# 8x8v2.net
KiCad netlist of a schematic drawn in EAGLE
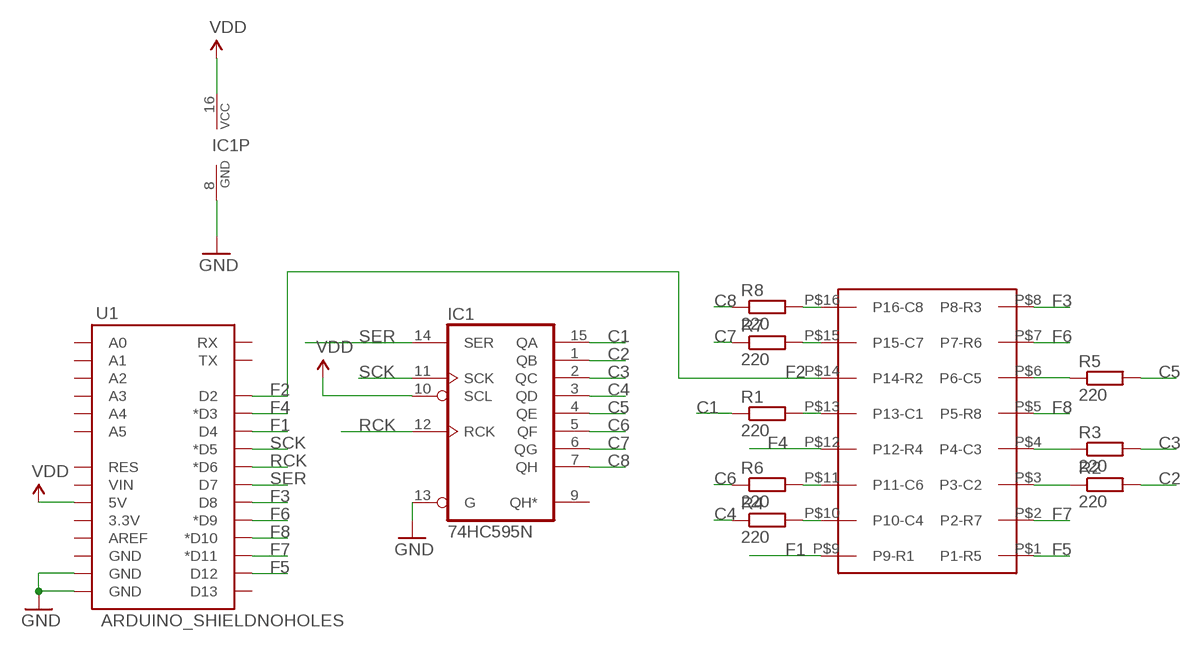
[diagram p0: schematic, sheet 1]

(export (version "E")
  (design (tool "Eeschema 10.0.6"))
  (components
    (comp (ref "IC1")
      (value "74HC595N")
      (footprint "eagle-import:DIL16")
      (libsource (lib "eagle-import") (part "74595NHC"))
    )
    (comp (ref "R1")
      (value "220")
      (footprint "eagle-import:0207_10")
      (libsource (lib "eagle-import") (part "R-EU_0207/10"))
    )
    (comp (ref "R2")
      (value "220")
      (footprint "eagle-import:0207_10")
      (libsource (lib "eagle-import") (part "R-EU_0207/10"))
    )
    (comp (ref "R3")
      (value "220")
      (footprint "eagle-import:0207_10")
      (libsource (lib "eagle-import") (part "R-EU_0207/10"))
    )
    (comp (ref "R4")
      (value "220")
      (footprint "eagle-import:0207_10")
      (libsource (lib "eagle-import") (part "R-EU_0207/10"))
    )
    (comp (ref "R5")
      (value "220")
      (footprint "eagle-import:0207_10")
      (libsource (lib "eagle-import") (part "R-EU_0207/10"))
    )
    (comp (ref "R6")
      (value "220")
      (footprint "eagle-import:0207_10")
      (libsource (lib "eagle-import") (part "R-EU_0207/10"))
    )
    (comp (ref "R7")
      (value "220")
      (footprint "eagle-import:0207_10")
      (libsource (lib "eagle-import") (part "R-EU_0207/10"))
    )
    (comp (ref "R8")
      (value "220")
      (footprint "eagle-import:0207_10")
      (libsource (lib "eagle-import") (part "R-EU_0207/10"))
    )
    (comp (ref "U$1")
      (value "MATRIX8X8")
      (footprint "eagle-import:MATRIX")
      (libsource (lib "eagle-import") (part "MATRIX8X8"))
    )
    (comp (ref "U1")
      (value "ARDUINO_SHIELDNOHOLES")
      (footprint "eagle-import:DUEMILANOVE_SHIELD_NOHOLES")
      (libsource (lib "eagle-import") (part "ARDUINO_SHIELDNOHOLES"))
    )
  )
  (nets
    (net (code "1") (name "/C1") (class "Default")
      (node (ref "IC1") (pin "15") (pinfunction "QA_15") (pintype "tri_state"))
      (node (ref "R1") (pin "1") (pinfunction "1_1") (pintype "passive"))
    )
    (net (code "2") (name "/C2") (class "Default")
      (node (ref "IC1") (pin "1") (pinfunction "QB_1") (pintype "tri_state"))
      (node (ref "R2") (pin "2") (pinfunction "2_2") (pintype "passive"))
    )
    (net (code "3") (name "/C3") (class "Default")
      (node (ref "IC1") (pin "2") (pinfunction "QC_2") (pintype "tri_state"))
      (node (ref "R3") (pin "2") (pinfunction "2_2") (pintype "passive"))
    )
    (net (code "4") (name "/C4") (class "Default")
      (node (ref "IC1") (pin "3") (pinfunction "QD_3") (pintype "tri_state"))
      (node (ref "R4") (pin "1") (pinfunction "1_1") (pintype "passive"))
    )
    (net (code "5") (name "/C5") (class "Default")
      (node (ref "IC1") (pin "4") (pinfunction "QE_4") (pintype "tri_state"))
      (node (ref "R5") (pin "2") (pinfunction "2_2") (pintype "passive"))
    )
    (net (code "6") (name "/C6") (class "Default")
      (node (ref "IC1") (pin "5") (pinfunction "QF_5") (pintype "tri_state"))
      (node (ref "R6") (pin "1") (pinfunction "1_1") (pintype "passive"))
    )
    (net (code "7") (name "/C7") (class "Default")
      (node (ref "IC1") (pin "6") (pinfunction "QG_6") (pintype "tri_state"))
      (node (ref "R7") (pin "1") (pinfunction "1_1") (pintype "passive"))
    )
    (net (code "8") (name "/C8") (class "Default")
      (node (ref "IC1") (pin "7") (pinfunction "QH_7") (pintype "tri_state"))
      (node (ref "R8") (pin "1") (pinfunction "1_1") (pintype "passive"))
    )
    (net (code "9") (name "/F1") (class "Default")
      (node (ref "U$1") (pin "P$9") (pinfunction "P9-R1_P$9") (pintype "bidirectional"))
      (node (ref "U1") (pin "D4") (pinfunction "D4_D4") (pintype "bidirectional"))
    )
    (net (code "10") (name "/F2") (class "Default")
      (node (ref "U$1") (pin "P$14") (pinfunction "P14-R2_P$14") (pintype "bidirectional"))
      (node (ref "U1") (pin "D2") (pinfunction "D2_D2") (pintype "bidirectional"))
    )
    (net (code "11") (name "/F3") (class "Default")
      (node (ref "U$1") (pin "P$8") (pinfunction "P8-R3_P$8") (pintype "bidirectional"))
      (node (ref "U1") (pin "D8") (pinfunction "D8_D8") (pintype "bidirectional"))
    )
    (net (code "12") (name "/F4") (class "Default")
      (node (ref "U$1") (pin "P$12") (pinfunction "P12-R4_P$12") (pintype "bidirectional"))
      (node (ref "U1") (pin "D3") (pinfunction "*D3_D3") (pintype "bidirectional"))
    )
    (net (code "13") (name "/F5") (class "Default")
      (node (ref "U$1") (pin "P$1") (pinfunction "P1-R5_P$1") (pintype "bidirectional"))
      (node (ref "U1") (pin "D12") (pinfunction "D12_D12") (pintype "bidirectional"))
    )
    (net (code "14") (name "/F6") (class "Default")
      (node (ref "U$1") (pin "P$7") (pinfunction "P7-R6_P$7") (pintype "bidirectional"))
      (node (ref "U1") (pin "D9") (pinfunction "*D9_D9") (pintype "bidirectional"))
    )
    (net (code "15") (name "/F7") (class "Default")
      (node (ref "U$1") (pin "P$2") (pinfunction "P2-R7_P$2") (pintype "bidirectional"))
      (node (ref "U1") (pin "D11") (pinfunction "*D11_D11") (pintype "bidirectional"))
    )
    (net (code "16") (name "/F8") (class "Default")
      (node (ref "U$1") (pin "P$5") (pinfunction "P5-R8_P$5") (pintype "bidirectional"))
      (node (ref "U1") (pin "D10") (pinfunction "*D10_D10") (pintype "bidirectional"))
    )
    (net (code "17") (name "/RCK") (class "Default")
      (node (ref "IC1") (pin "12") (pinfunction "RCK_12") (pintype "input"))
      (node (ref "U1") (pin "D6") (pinfunction "*D6_D6") (pintype "bidirectional"))
    )
    (net (code "18") (name "/SCK") (class "Default")
      (node (ref "IC1") (pin "11") (pinfunction "SCK_11") (pintype "input"))
      (node (ref "U1") (pin "D5") (pinfunction "*D5_D5") (pintype "bidirectional"))
    )
    (net (code "19") (name "/SER") (class "Default")
      (node (ref "IC1") (pin "14") (pinfunction "SER_14") (pintype "input"))
      (node (ref "U1") (pin "D7") (pinfunction "D7_D7") (pintype "bidirectional"))
    )
    (net (code "20") (name "GND") (class "Default")
      (node (ref "IC1") (pin "13") (pinfunction "G_13") (pintype "input"))
      (node (ref "IC1") (pin "8") (pinfunction "GND_8") (pintype "power_in"))
      (node (ref "U1") (pin "GND@0") (pinfunction "GND_GND@0") (pintype "bidirectional"))
      (node (ref "U1") (pin "GND@1") (pinfunction "GND_GND@1") (pintype "bidirectional"))
    )
    (net (code "21") (name "Net-(U$1-P3-C2)") (class "Default")
      (node (ref "R2") (pin "1") (pinfunction "1_1") (pintype "passive"))
      (node (ref "U$1") (pin "P$3") (pinfunction "P3-C2_P$3") (pintype "bidirectional"))
    )
    (net (code "22") (name "Net-(U$1-P4-C3)") (class "Default")
      (node (ref "R3") (pin "1") (pinfunction "1_1") (pintype "passive"))
      (node (ref "U$1") (pin "P$4") (pinfunction "P4-C3_P$4") (pintype "bidirectional"))
    )
    (net (code "23") (name "Net-(U$1-P6-C5)") (class "Default")
      (node (ref "R5") (pin "1") (pinfunction "1_1") (pintype "passive"))
      (node (ref "U$1") (pin "P$6") (pinfunction "P6-C5_P$6") (pintype "bidirectional"))
    )
    (net (code "24") (name "Net-(U$1-P10-C4)") (class "Default")
      (node (ref "R4") (pin "2") (pinfunction "2_2") (pintype "passive"))
      (node (ref "U$1") (pin "P$10") (pinfunction "P10-C4_P$10") (pintype "bidirectional"))
    )
    (net (code "25") (name "Net-(U$1-P11-C6)") (class "Default")
      (node (ref "R6") (pin "2") (pinfunction "2_2") (pintype "passive"))
      (node (ref "U$1") (pin "P$11") (pinfunction "P11-C6_P$11") (pintype "bidirectional"))
    )
    (net (code "26") (name "Net-(U$1-P13-C1)") (class "Default")
      (node (ref "R1") (pin "2") (pinfunction "2_2") (pintype "passive"))
      (node (ref "U$1") (pin "P$13") (pinfunction "P13-C1_P$13") (pintype "bidirectional"))
    )
    (net (code "27") (name "Net-(U$1-P15-C7)") (class "Default")
      (node (ref "R7") (pin "2") (pinfunction "2_2") (pintype "passive"))
      (node (ref "U$1") (pin "P$15") (pinfunction "P15-C7_P$15") (pintype "bidirectional"))
    )
    (net (code "28") (name "Net-(U$1-P16-C8)") (class "Default")
      (node (ref "R8") (pin "2") (pinfunction "2_2") (pintype "passive"))
      (node (ref "U$1") (pin "P$16") (pinfunction "P16-C8_P$16") (pintype "bidirectional"))
    )
    (net (code "29") (name "VDD") (class "Default")
      (node (ref "IC1") (pin "10") (pinfunction "SCL_10") (pintype "input"))
      (node (ref "IC1") (pin "16") (pinfunction "VCC_16") (pintype "power_in"))
      (node (ref "U1") (pin "5V") (pinfunction "5V_5V") (pintype "bidirectional"))
    )
    (net (code "30") (name "unconnected-(IC1A-QH*-Pad9)") (class "Default")
      (node (ref "IC1") (pin "9") (pinfunction "QH*_9") (pintype "tri_state"))
    )
    (net (code "31") (name "unconnected-(U1-GND-PadGND@2)") (class "Default")
      (node (ref "U1") (pin "GND@2") (pinfunction "GND_GND@2") (pintype "bidirectional"))
    )
    (net (code "32") (name "unconnected-(U1-Pad3.3V)") (class "Default")
      (node (ref "U1") (pin "3.3V") (pinfunction "3.3V_3.3V") (pintype "bidirectional"))
    )
    (net (code "33") (name "unconnected-(U1-PadA0)") (class "Default")
      (node (ref "U1") (pin "A0") (pinfunction "A0_A0") (pintype "bidirectional"))
    )
    (net (code "34") (name "unconnected-(U1-PadA1)") (class "Default")
      (node (ref "U1") (pin "A1") (pinfunction "A1_A1") (pintype "bidirectional"))
    )
    (net (code "35") (name "unconnected-(U1-PadA2)") (class "Default")
      (node (ref "U1") (pin "A2") (pinfunction "A2_A2") (pintype "bidirectional"))
    )
    (net (code "36") (name "unconnected-(U1-PadA3)") (class "Default")
      (node (ref "U1") (pin "A3") (pinfunction "A3_A3") (pintype "bidirectional"))
    )
    (net (code "37") (name "unconnected-(U1-PadA4)") (class "Default")
      (node (ref "U1") (pin "A4") (pinfunction "A4_A4") (pintype "bidirectional"))
    )
    (net (code "38") (name "unconnected-(U1-PadA5)") (class "Default")
      (node (ref "U1") (pin "A5") (pinfunction "A5_A5") (pintype "bidirectional"))
    )
    (net (code "39") (name "unconnected-(U1-PadAREF)") (class "Default")
      (node (ref "U1") (pin "AREF") (pinfunction "AREF_AREF") (pintype "bidirectional"))
    )
    (net (code "40") (name "unconnected-(U1-PadD13)") (class "Default")
      (node (ref "U1") (pin "D13") (pinfunction "D13_D13") (pintype "bidirectional"))
    )
    (net (code "41") (name "unconnected-(U1-PadRES)") (class "Default")
      (node (ref "U1") (pin "RES") (pinfunction "RES_RES") (pintype "bidirectional"))
    )
    (net (code "42") (name "unconnected-(U1-PadRX)") (class "Default")
      (node (ref "U1") (pin "RX") (pinfunction "RX_RX") (pintype "bidirectional"))
    )
    (net (code "43") (name "unconnected-(U1-PadTX)") (class "Default")
      (node (ref "U1") (pin "TX") (pinfunction "TX_TX") (pintype "bidirectional"))
    )
    (net (code "44") (name "unconnected-(U1-PadVIN)") (class "Default")
      (node (ref "U1") (pin "VIN") (pinfunction "VIN_VIN") (pintype "bidirectional"))
    )
  )
)
